# main.net
KiCad netlist of a schematic drawn in EAGLE
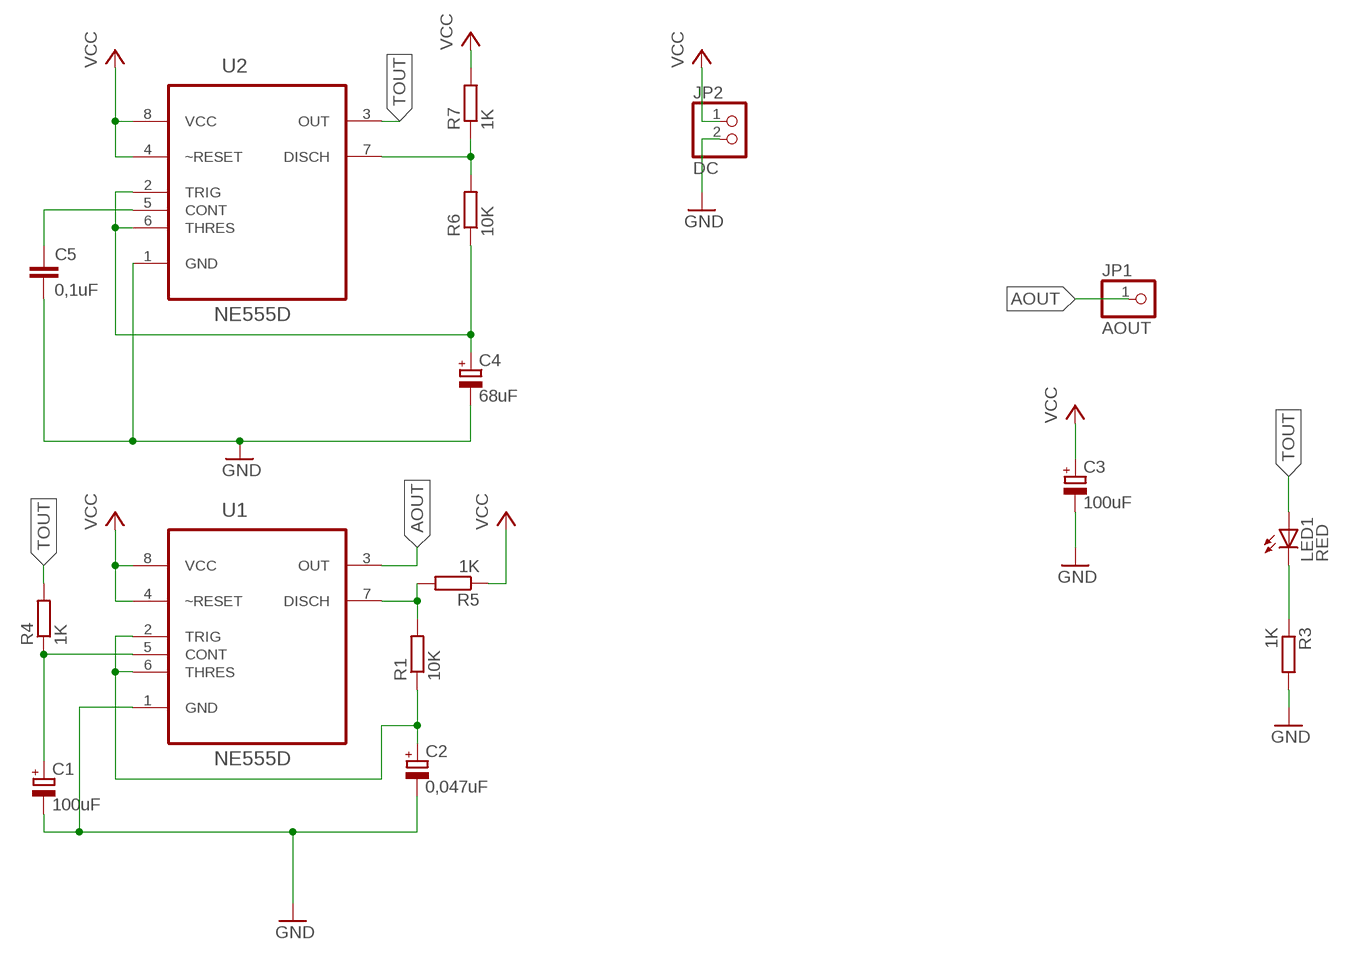
[diagram p0: schematic, sheet 1]

(export (version "E")
  (design (tool "Eeschema 10.0.6"))
  (components
    (comp (ref "C1")
      (value "100uF")
      (footprint "eagle-import:E3,5-8")
      (libsource (lib "eagle-import") (part "CPOL-EUE3.5-8"))
    )
    (comp (ref "C2")
      (value "0,047uF")
      (footprint "eagle-import:E3,5-8")
      (libsource (lib "eagle-import") (part "CPOL-EUE3.5-8"))
    )
    (comp (ref "C3")
      (value "100uF")
      (footprint "eagle-import:E3,5-8")
      (libsource (lib "eagle-import") (part "CPOL-EUE3.5-8"))
    )
    (comp (ref "C4")
      (value "68uF")
      (footprint "eagle-import:E3,5-8")
      (libsource (lib "eagle-import") (part "CPOL-EUE3.5-8"))
    )
    (comp (ref "C5")
      (value "0,1uF")
      (footprint "eagle-import:C025-025X050")
      (libsource (lib "eagle-import") (part "C-EU025-025X050"))
    )
    (comp (ref "JP1")
      (value "AOUT")
      (footprint "eagle-import:1X01")
      (libsource (lib "eagle-import") (part "PINHD-1X1"))
    )
    (comp (ref "JP2")
      (value "DC")
      (footprint "eagle-import:1X02")
      (libsource (lib "eagle-import") (part "PINHD-1X2"))
    )
    (comp (ref "LED1")
      (value "RED")
      (footprint "eagle-import:CHIPLED_0805")
      (libsource (lib "eagle-import") (part "LEDCHIPLED_0805"))
    )
    (comp (ref "R1")
      (value "10K")
      (footprint "eagle-import:R0805")
      (libsource (lib "eagle-import") (part "R-EU_R0805"))
    )
    (comp (ref "R3")
      (value "1K")
      (footprint "eagle-import:R0805")
      (libsource (lib "eagle-import") (part "R-EU_R0805"))
    )
    (comp (ref "R4")
      (value "1K")
      (footprint "eagle-import:R0805")
      (libsource (lib "eagle-import") (part "R-EU_R0805"))
    )
    (comp (ref "R5")
      (value "1K")
      (footprint "eagle-import:R0805")
      (libsource (lib "eagle-import") (part "R-EU_R0805"))
    )
    (comp (ref "R6")
      (value "10K")
      (footprint "eagle-import:R0805")
      (libsource (lib "eagle-import") (part "R-EU_R0805"))
    )
    (comp (ref "R7")
      (value "1K")
      (footprint "eagle-import:R0805")
      (libsource (lib "eagle-import") (part "R-EU_R0805"))
    )
    (comp (ref "U1")
      (value "NE555D")
      (footprint "eagle-import:SOIC127P600X175-8N")
      (libsource (lib "eagle-import") (part "NE555D"))
    )
    (comp (ref "U2")
      (value "NE555D")
      (footprint "eagle-import:SOIC127P600X175-8N")
      (libsource (lib "eagle-import") (part "NE555D"))
    )
  )
  (nets
    (net (code "1") (name "AOUT") (class "Default")
      (node (ref "JP1") (pin "1") (pinfunction "1_1") (pintype "passive"))
      (node (ref "U1") (pin "3") (pinfunction "OUT_3") (pintype "output"))
    )
    (net (code "2") (name "GND") (class "Default")
      (node (ref "C1") (pin "-") (pinfunction "-_-") (pintype "passive"))
      (node (ref "C2") (pin "-") (pinfunction "-_-") (pintype "passive"))
      (node (ref "C3") (pin "-") (pinfunction "-_-") (pintype "passive"))
      (node (ref "C4") (pin "-") (pinfunction "-_-") (pintype "passive"))
      (node (ref "C5") (pin "2") (pinfunction "2_2") (pintype "passive"))
      (node (ref "JP2") (pin "2") (pinfunction "2_2") (pintype "passive"))
      (node (ref "R3") (pin "2") (pinfunction "2_2") (pintype "passive"))
      (node (ref "U1") (pin "1") (pinfunction "GND_1") (pintype "passive"))
      (node (ref "U2") (pin "1") (pinfunction "GND_1") (pintype "passive"))
    )
    (net (code "3") (name "Net-(LED1-PadC)") (class "Default")
      (node (ref "LED1") (pin "C") (pinfunction "C_C") (pintype "passive"))
      (node (ref "R3") (pin "1") (pinfunction "1_1") (pintype "passive"))
    )
    (net (code "4") (name "Net-(U1-CONT)") (class "Default")
      (node (ref "C1") (pin "+") (pinfunction "+_+") (pintype "passive"))
      (node (ref "R4") (pin "1") (pinfunction "1_1") (pintype "passive"))
      (node (ref "U1") (pin "5") (pinfunction "CONT_5") (pintype "passive"))
    )
    (net (code "5") (name "Net-(U1-DISCH)") (class "Default")
      (node (ref "R1") (pin "2") (pinfunction "2_2") (pintype "passive"))
      (node (ref "R5") (pin "2") (pinfunction "2_2") (pintype "passive"))
      (node (ref "U1") (pin "7") (pinfunction "DISCH_7") (pintype "passive"))
    )
    (net (code "6") (name "Net-(U1-THRES)") (class "Default")
      (node (ref "C2") (pin "+") (pinfunction "+_+") (pintype "passive"))
      (node (ref "R1") (pin "1") (pinfunction "1_1") (pintype "passive"))
      (node (ref "U1") (pin "2") (pinfunction "TRIG_2") (pintype "input"))
      (node (ref "U1") (pin "6") (pinfunction "THRES_6") (pintype "input"))
    )
    (net (code "7") (name "Net-(U2-CONT)") (class "Default")
      (node (ref "C5") (pin "1") (pinfunction "1_1") (pintype "passive"))
      (node (ref "U2") (pin "5") (pinfunction "CONT_5") (pintype "passive"))
    )
    (net (code "8") (name "Net-(U2-DISCH)") (class "Default")
      (node (ref "R6") (pin "2") (pinfunction "2_2") (pintype "passive"))
      (node (ref "R7") (pin "1") (pinfunction "1_1") (pintype "passive"))
      (node (ref "U2") (pin "7") (pinfunction "DISCH_7") (pintype "passive"))
    )
    (net (code "9") (name "Net-(U2-THRES)") (class "Default")
      (node (ref "C4") (pin "+") (pinfunction "+_+") (pintype "passive"))
      (node (ref "R6") (pin "1") (pinfunction "1_1") (pintype "passive"))
      (node (ref "U2") (pin "2") (pinfunction "TRIG_2") (pintype "input"))
      (node (ref "U2") (pin "6") (pinfunction "THRES_6") (pintype "input"))
    )
    (net (code "10") (name "TOUT") (class "Default")
      (node (ref "LED1") (pin "A") (pinfunction "A_A") (pintype "passive"))
      (node (ref "R4") (pin "2") (pinfunction "2_2") (pintype "passive"))
      (node (ref "U2") (pin "3") (pinfunction "OUT_3") (pintype "output"))
    )
    (net (code "11") (name "VCC") (class "Default")
      (node (ref "C3") (pin "+") (pinfunction "+_+") (pintype "passive"))
      (node (ref "JP2") (pin "1") (pinfunction "1_1") (pintype "passive"))
      (node (ref "R5") (pin "1") (pinfunction "1_1") (pintype "passive"))
      (node (ref "R7") (pin "2") (pinfunction "2_2") (pintype "passive"))
      (node (ref "U1") (pin "4") (pinfunction "~{RESET}_4") (pintype "input"))
      (node (ref "U1") (pin "8") (pinfunction "VCC_8") (pintype "power_in"))
      (node (ref "U2") (pin "4") (pinfunction "~{RESET}_4") (pintype "input"))
      (node (ref "U2") (pin "8") (pinfunction "VCC_8") (pintype "power_in"))
    )
  )
)
